# untitled.net
KiCad netlist of a schematic drawn in EAGLE
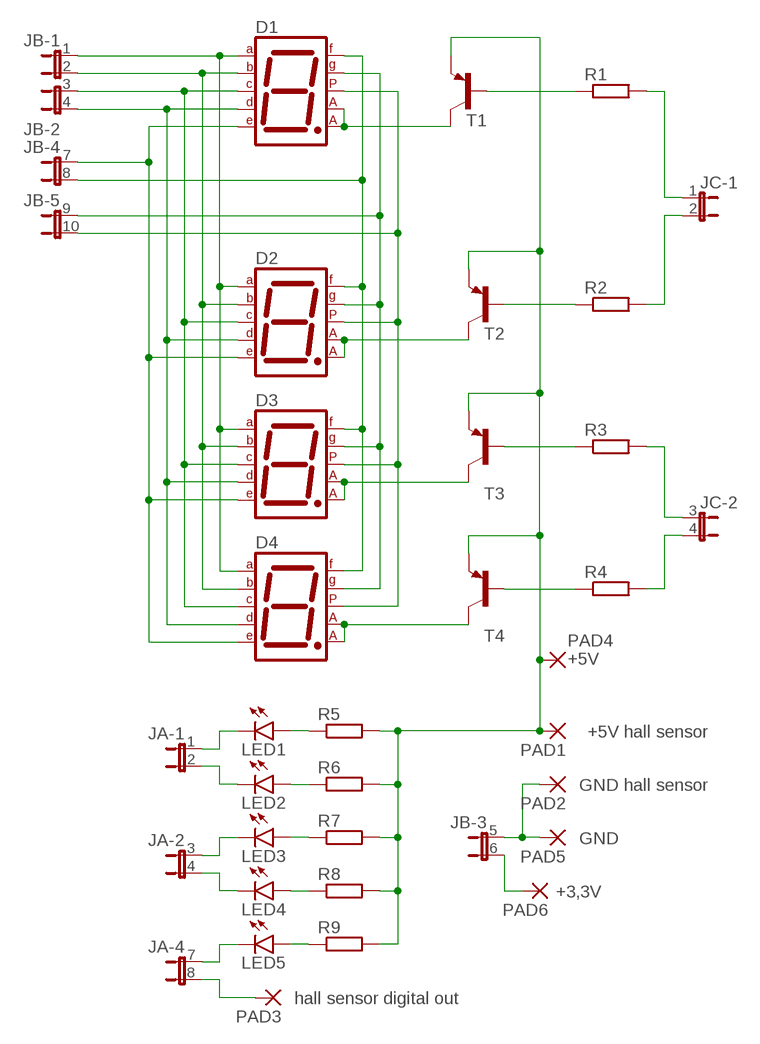
[diagram p0: schematic, sheet 1]

(export (version "E")
  (design (tool "Eeschema 10.0.6"))
  (components
    (comp (ref "D1")
      (value "7SEG-CA")
      (footprint "eagle-import:7SEG-13")
      (libsource (lib "eagle-import") (part "7SEG-CA"))
    )
    (comp (ref "D2")
      (value "7SEG-CA")
      (footprint "eagle-import:7SEG-13")
      (libsource (lib "eagle-import") (part "7SEG-CA"))
    )
    (comp (ref "D3")
      (value "7SEG-CA")
      (footprint "eagle-import:7SEG-13")
      (libsource (lib "eagle-import") (part "7SEG-CA"))
    )
    (comp (ref "D4")
      (value "7SEG-CA")
      (footprint "eagle-import:7SEG-13")
      (libsource (lib "eagle-import") (part "7SEG-CA"))
    )
    (comp (ref "JA")
      (value "JP6QE")
      (footprint "eagle-import:JP6Q")
      (libsource (lib "eagle-import") (part "JP6QE"))
    )
    (comp (ref "JB")
      (value "JP6QE")
      (footprint "eagle-import:JP6Q")
      (libsource (lib "eagle-import") (part "JP6QE"))
    )
    (comp (ref "JC")
      (value "JP6QE")
      (footprint "eagle-import:JP6Q")
      (libsource (lib "eagle-import") (part "JP6QE"))
    )
    (comp (ref "LED1")
      (value "LED5MM")
      (footprint "eagle-import:LED5MM")
      (libsource (lib "eagle-import") (part "LED5MM"))
    )
    (comp (ref "LED2")
      (value "LED5MM")
      (footprint "eagle-import:LED5MM")
      (libsource (lib "eagle-import") (part "LED5MM"))
    )
    (comp (ref "LED3")
      (value "LED5MM")
      (footprint "eagle-import:LED5MM")
      (libsource (lib "eagle-import") (part "LED5MM"))
    )
    (comp (ref "LED4")
      (value "LED5MM")
      (footprint "eagle-import:LED5MM")
      (libsource (lib "eagle-import") (part "LED5MM"))
    )
    (comp (ref "LED5")
      (value "LED5MM")
      (footprint "eagle-import:LED5MM")
      (libsource (lib "eagle-import") (part "LED5MM"))
    )
    (comp (ref "PAD1")
      (value "+5V hall sensor")
      (footprint "eagle-import:2,15_1,0")
      (libsource (lib "eagle-import") (part "WIREPAD2,15/1,0"))
    )
    (comp (ref "PAD2")
      (value "GND hall sensor")
      (footprint "eagle-import:2,15_1,0")
      (libsource (lib "eagle-import") (part "WIREPAD2,15/1,0"))
    )
    (comp (ref "PAD3")
      (value "hall sensor digital out")
      (footprint "eagle-import:2,15_1,0")
      (libsource (lib "eagle-import") (part "WIREPAD2,15/1,0"))
    )
    (comp (ref "PAD4")
      (value "+5V")
      (footprint "eagle-import:2,15_1,0")
      (libsource (lib "eagle-import") (part "WIREPAD2,15/1,0"))
    )
    (comp (ref "PAD5")
      (value "GND")
      (footprint "eagle-import:2,15_1,0")
      (libsource (lib "eagle-import") (part "WIREPAD2,15/1,0"))
    )
    (comp (ref "PAD6")
      (value "+3,3V")
      (footprint "eagle-import:2,15_1,0")
      (libsource (lib "eagle-import") (part "WIREPAD2,15/1,0"))
    )
    (comp (ref "R1")
      (value "R-EU_0204/7")
      (footprint "eagle-import:0204_7")
      (libsource (lib "eagle-import") (part "R-EU_0204/7"))
    )
    (comp (ref "R2")
      (value "R-EU_0204/7")
      (footprint "eagle-import:0204_7")
      (libsource (lib "eagle-import") (part "R-EU_0204/7"))
    )
    (comp (ref "R3")
      (value "R-EU_0204/7")
      (footprint "eagle-import:0204_7")
      (libsource (lib "eagle-import") (part "R-EU_0204/7"))
    )
    (comp (ref "R4")
      (value "R-EU_0204/7")
      (footprint "eagle-import:0204_7")
      (libsource (lib "eagle-import") (part "R-EU_0204/7"))
    )
    (comp (ref "R5")
      (value "R-EU_0204/7")
      (footprint "eagle-import:0204_7")
      (libsource (lib "eagle-import") (part "R-EU_0204/7"))
    )
    (comp (ref "R6")
      (value "R-EU_0204/7")
      (footprint "eagle-import:0204_7")
      (libsource (lib "eagle-import") (part "R-EU_0204/7"))
    )
    (comp (ref "R7")
      (value "R-EU_0204/7")
      (footprint "eagle-import:0204_7")
      (libsource (lib "eagle-import") (part "R-EU_0204/7"))
    )
    (comp (ref "R8")
      (value "R-EU_0204/7")
      (footprint "eagle-import:0204_7")
      (libsource (lib "eagle-import") (part "R-EU_0204/7"))
    )
    (comp (ref "R9")
      (value "R-EU_0204/7")
      (footprint "eagle-import:0204_7")
      (libsource (lib "eagle-import") (part "R-EU_0204/7"))
    )
    (comp (ref "T1")
      (value "BC327-25-PNP-TO92-EBC")
      (footprint "eagle-import:TO92-EBC")
      (libsource (lib "eagle-import") (part "-PNP-TO92-EBCBC327-25"))
    )
    (comp (ref "T2")
      (value "BC327-25-PNP-TO92-EBC")
      (footprint "eagle-import:TO92-EBC")
      (libsource (lib "eagle-import") (part "-PNP-TO92-EBCBC327-25"))
    )
    (comp (ref "T3")
      (value "BC327-25-PNP-TO92-EBC")
      (footprint "eagle-import:TO92-EBC")
      (libsource (lib "eagle-import") (part "-PNP-TO92-EBCBC327-25"))
    )
    (comp (ref "T4")
      (value "BC327-25-PNP-TO92-EBC")
      (footprint "eagle-import:TO92-EBC")
      (libsource (lib "eagle-import") (part "-PNP-TO92-EBCBC327-25"))
    )
  )
  (nets
    (net (code "1") (name "Net-(D1-A)") (class "Default")
      (node (ref "D1") (pin "7") (pinfunction "A_7") (pintype "passive"))
      (node (ref "D2") (pin "7") (pinfunction "A_7") (pintype "passive"))
      (node (ref "D3") (pin "7") (pinfunction "A_7") (pintype "passive"))
      (node (ref "D4") (pin "7") (pinfunction "A_7") (pintype "passive"))
      (node (ref "JB") (pin "1") (pinfunction "1_1") (pintype "passive"))
    )
    (net (code "2") (name "Net-(D1-B)") (class "Default")
      (node (ref "D1") (pin "6") (pinfunction "B_6") (pintype "passive"))
      (node (ref "D2") (pin "6") (pinfunction "B_6") (pintype "passive"))
      (node (ref "D3") (pin "6") (pinfunction "B_6") (pintype "passive"))
      (node (ref "D4") (pin "6") (pinfunction "B_6") (pintype "passive"))
      (node (ref "JB") (pin "2") (pinfunction "2_2") (pintype "passive"))
    )
    (net (code "3") (name "Net-(D1-C)") (class "Default")
      (node (ref "D1") (pin "4") (pinfunction "C_4") (pintype "passive"))
      (node (ref "D2") (pin "4") (pinfunction "C_4") (pintype "passive"))
      (node (ref "D3") (pin "4") (pinfunction "C_4") (pintype "passive"))
      (node (ref "D4") (pin "4") (pinfunction "C_4") (pintype "passive"))
      (node (ref "JB") (pin "3") (pinfunction "1_3") (pintype "passive"))
    )
    (net (code "4") (name "Net-(D1-CA1)") (class "Default")
      (node (ref "D1") (pin "3") (pinfunction "CA1_3") (pintype "passive"))
      (node (ref "D1") (pin "8") (pinfunction "CA2_8") (pintype "passive"))
      (node (ref "T1") (pin "C") (pinfunction "C_C") (pintype "passive"))
    )
    (net (code "5") (name "Net-(D1-D)") (class "Default")
      (node (ref "D1") (pin "2") (pinfunction "D_2") (pintype "passive"))
      (node (ref "D2") (pin "2") (pinfunction "D_2") (pintype "passive"))
      (node (ref "D3") (pin "2") (pinfunction "D_2") (pintype "passive"))
      (node (ref "D4") (pin "2") (pinfunction "D_2") (pintype "passive"))
      (node (ref "JB") (pin "4") (pinfunction "2_4") (pintype "passive"))
    )
    (net (code "6") (name "Net-(D1-DP)") (class "Default")
      (node (ref "D1") (pin "5") (pinfunction "DP_5") (pintype "passive"))
      (node (ref "D2") (pin "5") (pinfunction "DP_5") (pintype "passive"))
      (node (ref "D3") (pin "5") (pinfunction "DP_5") (pintype "passive"))
      (node (ref "D4") (pin "5") (pinfunction "DP_5") (pintype "passive"))
      (node (ref "JB") (pin "10") (pinfunction "2_10") (pintype "passive"))
    )
    (net (code "7") (name "Net-(D1-E)") (class "Default")
      (node (ref "D1") (pin "1") (pinfunction "E_1") (pintype "passive"))
      (node (ref "D2") (pin "1") (pinfunction "E_1") (pintype "passive"))
      (node (ref "D3") (pin "1") (pinfunction "E_1") (pintype "passive"))
      (node (ref "D4") (pin "1") (pinfunction "E_1") (pintype "passive"))
      (node (ref "JB") (pin "7") (pinfunction "1_7") (pintype "passive"))
    )
    (net (code "8") (name "Net-(D1-F)") (class "Default")
      (node (ref "D1") (pin "9") (pinfunction "F_9") (pintype "passive"))
      (node (ref "D2") (pin "9") (pinfunction "F_9") (pintype "passive"))
      (node (ref "D3") (pin "9") (pinfunction "F_9") (pintype "passive"))
      (node (ref "D4") (pin "9") (pinfunction "F_9") (pintype "passive"))
      (node (ref "JB") (pin "8") (pinfunction "2_8") (pintype "passive"))
    )
    (net (code "9") (name "Net-(D1-G)") (class "Default")
      (node (ref "D1") (pin "10") (pinfunction "G_10") (pintype "passive"))
      (node (ref "D2") (pin "10") (pinfunction "G_10") (pintype "passive"))
      (node (ref "D3") (pin "10") (pinfunction "G_10") (pintype "passive"))
      (node (ref "D4") (pin "10") (pinfunction "G_10") (pintype "passive"))
      (node (ref "JB") (pin "9") (pinfunction "1_9") (pintype "passive"))
    )
    (net (code "10") (name "Net-(D2-CA1)") (class "Default")
      (node (ref "D2") (pin "3") (pinfunction "CA1_3") (pintype "passive"))
      (node (ref "D2") (pin "8") (pinfunction "CA2_8") (pintype "passive"))
      (node (ref "T2") (pin "C") (pinfunction "C_C") (pintype "passive"))
    )
    (net (code "11") (name "Net-(D3-CA1)") (class "Default")
      (node (ref "D3") (pin "3") (pinfunction "CA1_3") (pintype "passive"))
      (node (ref "D3") (pin "8") (pinfunction "CA2_8") (pintype "passive"))
      (node (ref "T3") (pin "C") (pinfunction "C_C") (pintype "passive"))
    )
    (net (code "12") (name "Net-(D4-CA1)") (class "Default")
      (node (ref "D4") (pin "3") (pinfunction "CA1_3") (pintype "passive"))
      (node (ref "D4") (pin "8") (pinfunction "CA2_8") (pintype "passive"))
      (node (ref "T4") (pin "C") (pinfunction "C_C") (pintype "passive"))
    )
    (net (code "13") (name "Net-(JAB-1)") (class "Default")
      (node (ref "JA") (pin "3") (pinfunction "1_3") (pintype "passive"))
      (node (ref "LED3") (pin "K") (pinfunction "C_K") (pintype "passive"))
    )
    (net (code "14") (name "Net-(JAB-2)") (class "Default")
      (node (ref "JA") (pin "4") (pinfunction "2_4") (pintype "passive"))
      (node (ref "LED4") (pin "K") (pinfunction "C_K") (pintype "passive"))
    )
    (net (code "15") (name "Net-(JAD-1)") (class "Default")
      (node (ref "JA") (pin "7") (pinfunction "1_7") (pintype "passive"))
      (node (ref "LED5") (pin "K") (pinfunction "C_K") (pintype "passive"))
    )
    (net (code "16") (name "Net-(JAD-2)") (class "Default")
      (node (ref "JA") (pin "8") (pinfunction "2_8") (pintype "passive"))
      (node (ref "PAD3") (pin "1") (pinfunction "P_1") (pintype "passive"))
    )
    (net (code "17") (name "Net-(JBC-1)") (class "Default")
      (node (ref "JB") (pin "5") (pinfunction "1_5") (pintype "passive"))
      (node (ref "PAD2") (pin "1") (pinfunction "P_1") (pintype "passive"))
      (node (ref "PAD5") (pin "1") (pinfunction "P_1") (pintype "passive"))
    )
    (net (code "18") (name "Net-(JBC-2)") (class "Default")
      (node (ref "JB") (pin "6") (pinfunction "2_6") (pintype "passive"))
      (node (ref "PAD6") (pin "1") (pinfunction "P_1") (pintype "passive"))
    )
    (net (code "19") (name "Net-(JC-Pad1)") (class "Default")
      (node (ref "JC") (pin "1") (pinfunction "1_1") (pintype "passive"))
      (node (ref "R1") (pin "2") (pinfunction "2_2") (pintype "passive"))
    )
    (net (code "20") (name "Net-(JC-Pad2)") (class "Default")
      (node (ref "JC") (pin "2") (pinfunction "2_2") (pintype "passive"))
      (node (ref "R2") (pin "2") (pinfunction "2_2") (pintype "passive"))
    )
    (net (code "21") (name "Net-(JCB-1)") (class "Default")
      (node (ref "JC") (pin "3") (pinfunction "1_3") (pintype "passive"))
      (node (ref "R3") (pin "2") (pinfunction "2_2") (pintype "passive"))
    )
    (net (code "22") (name "Net-(JCB-2)") (class "Default")
      (node (ref "JC") (pin "4") (pinfunction "2_4") (pintype "passive"))
      (node (ref "R4") (pin "2") (pinfunction "2_2") (pintype "passive"))
    )
    (net (code "23") (name "Net-(LED1-C)") (class "Default")
      (node (ref "JA") (pin "1") (pinfunction "1_1") (pintype "passive"))
      (node (ref "LED1") (pin "K") (pinfunction "C_K") (pintype "passive"))
    )
    (net (code "24") (name "Net-(LED1-PadA)") (class "Default")
      (node (ref "LED1") (pin "A") (pinfunction "A_A") (pintype "passive"))
      (node (ref "R5") (pin "1") (pinfunction "1_1") (pintype "passive"))
    )
    (net (code "25") (name "Net-(LED2-C)") (class "Default")
      (node (ref "JA") (pin "2") (pinfunction "2_2") (pintype "passive"))
      (node (ref "LED2") (pin "K") (pinfunction "C_K") (pintype "passive"))
    )
    (net (code "26") (name "Net-(LED2-PadA)") (class "Default")
      (node (ref "LED2") (pin "A") (pinfunction "A_A") (pintype "passive"))
      (node (ref "R6") (pin "1") (pinfunction "1_1") (pintype "passive"))
    )
    (net (code "27") (name "Net-(LED3-PadA)") (class "Default")
      (node (ref "LED3") (pin "A") (pinfunction "A_A") (pintype "passive"))
      (node (ref "R7") (pin "1") (pinfunction "1_1") (pintype "passive"))
    )
    (net (code "28") (name "Net-(LED4-PadA)") (class "Default")
      (node (ref "LED4") (pin "A") (pinfunction "A_A") (pintype "passive"))
      (node (ref "R8") (pin "1") (pinfunction "1_1") (pintype "passive"))
    )
    (net (code "29") (name "Net-(LED5-PadA)") (class "Default")
      (node (ref "LED5") (pin "A") (pinfunction "A_A") (pintype "passive"))
      (node (ref "R9") (pin "1") (pinfunction "1_1") (pintype "passive"))
    )
    (net (code "30") (name "Net-(PAD1-P)") (class "Default")
      (node (ref "PAD1") (pin "1") (pinfunction "P_1") (pintype "passive"))
      (node (ref "PAD4") (pin "1") (pinfunction "P_1") (pintype "passive"))
      (node (ref "R5") (pin "2") (pinfunction "2_2") (pintype "passive"))
      (node (ref "R6") (pin "2") (pinfunction "2_2") (pintype "passive"))
      (node (ref "R7") (pin "2") (pinfunction "2_2") (pintype "passive"))
      (node (ref "R8") (pin "2") (pinfunction "2_2") (pintype "passive"))
      (node (ref "R9") (pin "2") (pinfunction "2_2") (pintype "passive"))
      (node (ref "T1") (pin "E") (pinfunction "E_E") (pintype "passive"))
      (node (ref "T2") (pin "E") (pinfunction "E_E") (pintype "passive"))
      (node (ref "T3") (pin "E") (pinfunction "E_E") (pintype "passive"))
      (node (ref "T4") (pin "E") (pinfunction "E_E") (pintype "passive"))
    )
    (net (code "31") (name "Net-(R1-Pad1)") (class "Default")
      (node (ref "R1") (pin "1") (pinfunction "1_1") (pintype "passive"))
      (node (ref "T1") (pin "B") (pinfunction "B_B") (pintype "passive"))
    )
    (net (code "32") (name "Net-(R2-Pad1)") (class "Default")
      (node (ref "R2") (pin "1") (pinfunction "1_1") (pintype "passive"))
      (node (ref "T2") (pin "B") (pinfunction "B_B") (pintype "passive"))
    )
    (net (code "33") (name "Net-(R3-Pad1)") (class "Default")
      (node (ref "R3") (pin "1") (pinfunction "1_1") (pintype "passive"))
      (node (ref "T3") (pin "B") (pinfunction "B_B") (pintype "passive"))
    )
    (net (code "34") (name "Net-(R4-Pad1)") (class "Default")
      (node (ref "R4") (pin "1") (pinfunction "1_1") (pintype "passive"))
      (node (ref "T4") (pin "B") (pinfunction "B_B") (pintype "passive"))
    )
  )
)
